# PID.net
KiCad netlist of a schematic drawn in EasyEDA Pro
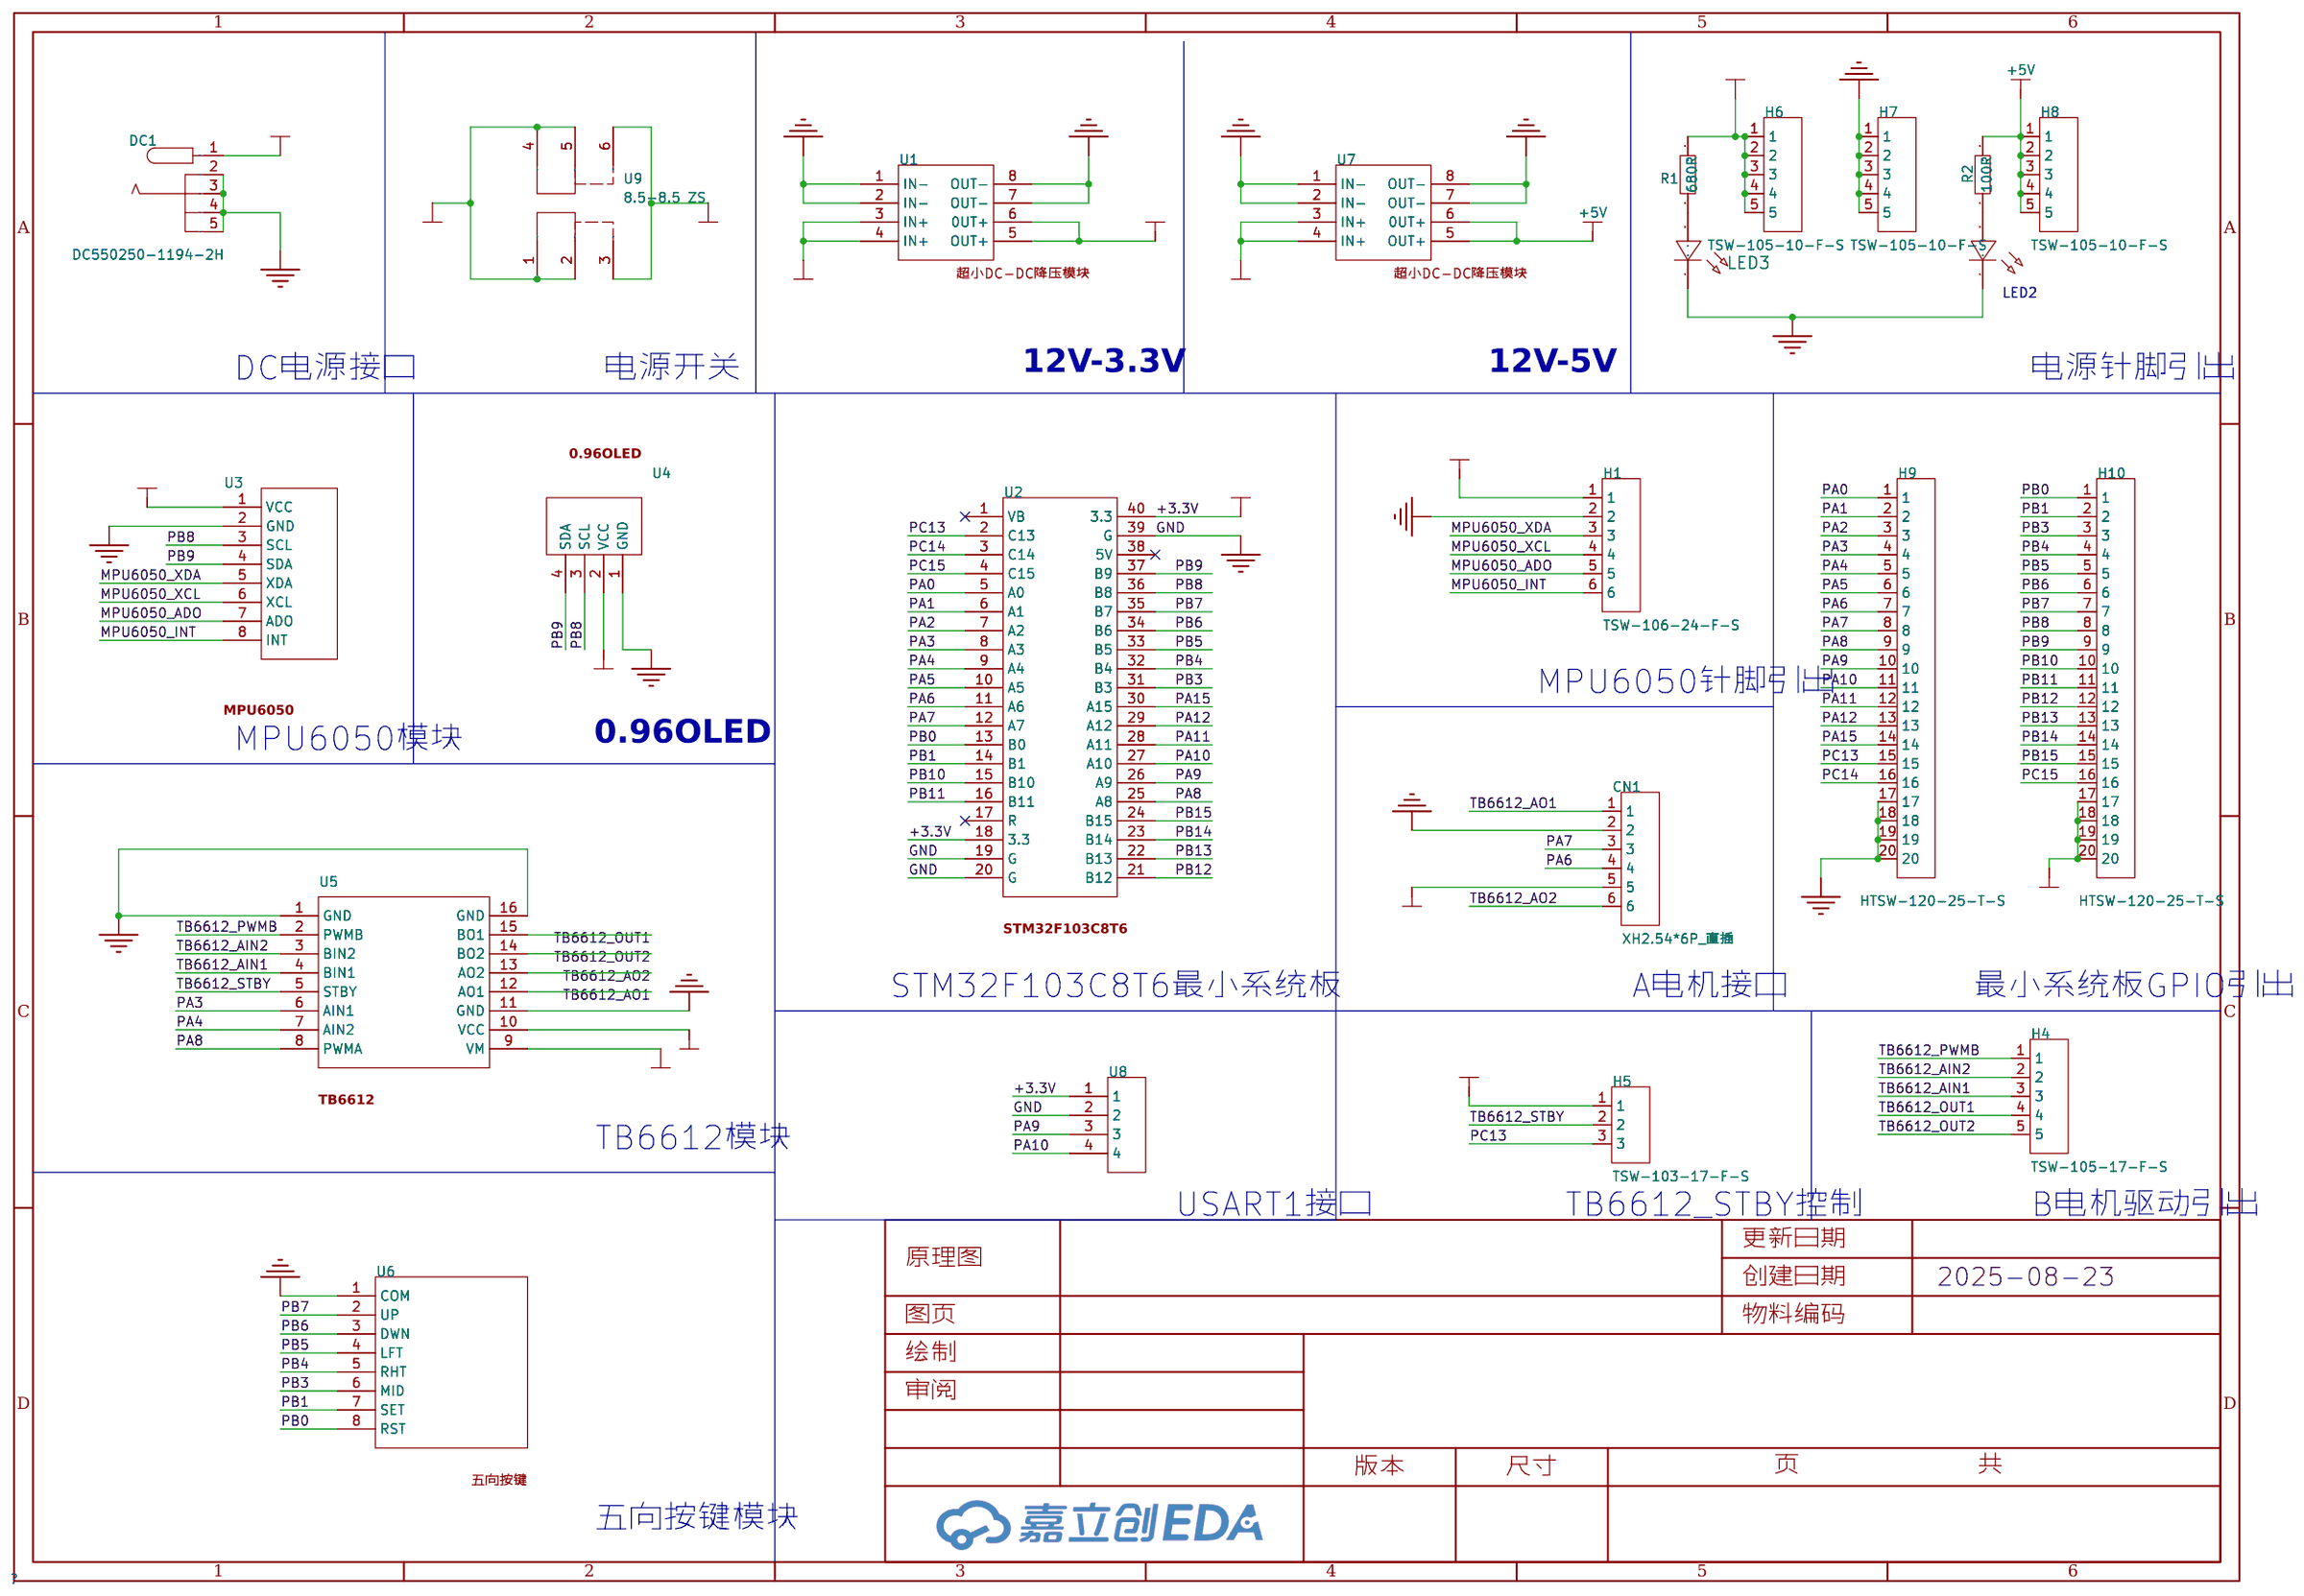
[diagram p0: schematic sheet]

(export (version "E")
  (design (tool "Eeschema 10.0.6"))
  (components
    (comp (ref "CN1")
      (value "XH2.54*6P_直插")
      (footprint "easyedapro:CONN-TH_XH2.54-6P")
      (libsource (lib "easyedapro") (part "XH2.54*6P_直插"))
    )
    (comp (ref "DC1")
      (value "DC550250-1194-2H")
      (footprint "easyedapro:DC-IN-TH_DC550250-1194-2H")
      (description "连接器类型:DC电源插座;")
      (fields (field (name "Manufacturer") "HDGC(华德共创)"))
      (libsource (lib "easyedapro") (part "DC550250-1194-2H"))
    )
    (comp (ref "H1")
      (value "TSW-106-24-F-S")
      (footprint "easyedapro:HDR-TH_MTSW-106-07-L-S-220")
      (description "间距:2.54mm;安装方式:直插;排数:单排;总PIN位数:6P;触头材质:磷青铜;触头镀层:锡;工作温度:-55°C~+125°C;颜色:黑色;")
      (fields (field (name "Manufacturer") "SAMTEC"))
      (libsource (lib "easyedapro") (part "TSW-106-24-F-S"))
    )
    (comp (ref "H4")
      (value "TSW-105-17-F-S")
      (footprint "easyedapro:HDR-TH_5P-P2.54_HTSW-105-08-F-S")
      (description "间距:2.54mm;安装方式:直插;排数:单排;总PIN位数:5P;触头材质:磷青铜;触头镀层:锡;工作温度:-55°C~+125°C;颜色:黑色;")
      (fields (field (name "Manufacturer") "SAMTEC"))
      (libsource (lib "easyedapro") (part "TSW-105-17-F-S"))
    )
    (comp (ref "H5")
      (value "TSW-103-17-F-S")
      (footprint "easyedapro:HDR-TH_3P-P2.54_HTSW-103-14-TM-S")
      (description "间距:2.54mm;安装方式:直插;排数:单排;总PIN位数:3P;触头材质:磷青铜;触头镀层:锡;工作温度:-55°C~+125°C;颜色:黑色;")
      (fields (field (name "Manufacturer") "SAMTEC"))
      (libsource (lib "easyedapro") (part "TSW-103-17-F-S"))
    )
    (comp (ref "H6")
      (value "TSW-105-10-F-S")
      (footprint "easyedapro:HDR-TH_5P-P2.54_HTSW-105-08-F-S")
      (description "间距:2.54mm;安装方式:直插;排数:单排;总PIN位数:5P;触头材质:磷青铜;触头镀层:锡;工作温度:-55°C~+125°C;颜色:黑色;")
      (fields (field (name "Manufacturer") "SAMTEC"))
      (libsource (lib "easyedapro") (part "TSW-105-10-F-S"))
    )
    (comp (ref "H7")
      (value "TSW-105-10-F-S")
      (footprint "easyedapro:HDR-TH_5P-P2.54_HTSW-105-08-F-S")
      (description "间距:2.54mm;安装方式:直插;排数:单排;总PIN位数:5P;触头材质:磷青铜;触头镀层:锡;工作温度:-55°C~+125°C;颜色:黑色;")
      (fields (field (name "Manufacturer") "SAMTEC"))
      (libsource (lib "easyedapro") (part "TSW-105-10-F-S"))
    )
    (comp (ref "H8")
      (value "TSW-105-10-F-S")
      (footprint "easyedapro:HDR-TH_5P-P2.54_HTSW-105-08-F-S")
      (description "间距:2.54mm;安装方式:直插;排数:单排;总PIN位数:5P;触头材质:磷青铜;触头镀层:锡;工作温度:-55°C~+125°C;颜色:黑色;")
      (fields (field (name "Manufacturer") "SAMTEC"))
      (libsource (lib "easyedapro") (part "TSW-105-10-F-S"))
    )
    (comp (ref "H9")
      (value "HTSW-120-25-T-S")
      (footprint "easyedapro:HDR-TH_TSW-120-22-L-S")
      (description "间距:2.54mm;安装方式:直插;排数:单排;总PIN位数:20P;触头材质:磷青铜;触头镀层:锡;工作温度:-55°C~+105°C;")
      (fields (field (name "Manufacturer") "SAMTEC"))
      (libsource (lib "easyedapro") (part "HTSW-120-25-T-S"))
    )
    (comp (ref "H10")
      (value "HTSW-120-25-T-S")
      (footprint "easyedapro:HDR-TH_TSW-120-22-L-S")
      (description "间距:2.54mm;安装方式:直插;排数:单排;总PIN位数:20P;触头材质:磷青铜;触头镀层:锡;工作温度:-55°C~+105°C;")
      (fields (field (name "Manufacturer") "SAMTEC"))
      (libsource (lib "easyedapro") (part "HTSW-120-25-T-S"))
    )
    (comp (ref "LED2")
      (value "~")
      (footprint "easyedapro:LED_0805")
      (libsource (lib "easyedapro") (part "LED_G"))
    )
    (comp (ref "LED3")
      (value "~")
      (footprint "easyedapro:LED_0805")
      (libsource (lib "easyedapro") (part "LED_R"))
    )
    (comp (ref "R1") (value "680R") (footprint "easyedapro:R0805") (libsource (lib "easyedapro") (part "电阻")))
    (comp (ref "R2") (value "100R") (footprint "easyedapro:R0805") (libsource (lib "easyedapro") (part "电阻")))
    (comp (ref "U1")
      (value "~")
      (footprint "easyedapro:12V-3.3V")
      (libsource (lib "easyedapro") (part "12V-3.3V"))
    )
    (comp (ref "U2")
      (value "~")
      (footprint "easyedapro:F103C8T6")
      (libsource (lib "easyedapro") (part "f103c8t6"))
    )
    (comp (ref "U3")
      (value "~")
      (footprint "easyedapro:MPU6050")
      (libsource (lib "easyedapro") (part "MPU6050"))
    )
    (comp (ref "U4")
      (value "~")
      (footprint "easyedapro:0.96OLED")
      (libsource (lib "easyedapro") (part "0.96OLED"))
    )
    (comp (ref "U5") (value "~") (footprint "easyedapro:电机驱动") (libsource (lib "easyedapro") (part "电机驱动")))
    (comp (ref "U6") (value "~") (footprint "easyedapro:五向按键") (libsource (lib "easyedapro") (part "五向按键")))
    (comp (ref "U7")
      (value "~")
      (footprint "easyedapro:12V-3.3V")
      (libsource (lib "easyedapro") (part "12V-3.3V"))
    )
    (comp (ref "U8") (value "~") (footprint "easyedapro:1x4") (libsource (lib "easyedapro") (part "1x4")))
    (comp (ref "U9")
      (value "8.5-8.5 ZS")
      (footprint "easyedapro:SW-TH_6P-L8.5-W8.5-P2.50_8.5-8.5-ZS")
      (description "电路结构:双刀双掷;自锁/无锁:自锁;安装方式:直插;触点电流:100mA;额定电压:30V;带灯:不带;作用力:1.8N;工作寿命:5千次;")
      (fields (field (name "Manufacturer") "SHOU HAN(首韩)"))
      (libsource (lib "easyedapro") (part "8.5-8.5 ZS"))
    )
  )
  (nets
    (net (code "1") (name "+3.3V") (class "Default")
      (node (ref "CN1") (pin "5") (pinfunction "5_5") (pintype "unspecified"))
      (node (ref "H1") (pin "1") (pinfunction "1_1") (pintype "unspecified"))
      (node (ref "H10") (pin "17") (pinfunction "17_17") (pintype "unspecified"))
      (node (ref "H10") (pin "18") (pinfunction "18_18") (pintype "unspecified"))
      (node (ref "H10") (pin "19") (pinfunction "19_19") (pintype "unspecified"))
      (node (ref "H10") (pin "20") (pinfunction "20_20") (pintype "unspecified"))
      (node (ref "H5") (pin "1") (pinfunction "1_1") (pintype "unspecified"))
      (node (ref "U1") (pin "5") (pinfunction "OUT+_5") (pintype "input"))
      (node (ref "U1") (pin "6") (pinfunction "0UT+_6") (pintype "input"))
      (node (ref "U2") (pin "18") (pinfunction "3.3_18") (pintype "input"))
      (node (ref "U2") (pin "40") (pinfunction "3.3_40") (pintype "input"))
      (node (ref "U3") (pin "1") (pinfunction "VCC_1") (pintype "input"))
      (node (ref "U4") (pin "2") (pinfunction "VCC_2") (pintype "input"))
      (node (ref "U5") (pin "10") (pinfunction "VCC_10") (pintype "input"))
      (node (ref "U8") (pin "1") (pinfunction "1_1") (pintype "input"))
    )
    (net (code "2") (name "+5V") (class "Default")
      (node (ref "H8") (pin "1") (pinfunction "1_1") (pintype "unspecified"))
      (node (ref "H8") (pin "2") (pinfunction "2_2") (pintype "unspecified"))
      (node (ref "H8") (pin "3") (pinfunction "3_3") (pintype "unspecified"))
      (node (ref "H8") (pin "4") (pinfunction "4_4") (pintype "unspecified"))
      (node (ref "H8") (pin "5") (pinfunction "5_5") (pintype "unspecified"))
      (node (ref "R2") (pin "2") (pinfunction "2_2") (pintype "input"))
      (node (ref "U7") (pin "5") (pinfunction "OUT+_5") (pintype "input"))
      (node (ref "U7") (pin "6") (pinfunction "0UT+_6") (pintype "input"))
    )
    (net (code "3") (name "+12V") (class "Default")
      (node (ref "H6") (pin "1") (pinfunction "1_1") (pintype "unspecified"))
      (node (ref "H6") (pin "2") (pinfunction "2_2") (pintype "unspecified"))
      (node (ref "H6") (pin "3") (pinfunction "3_3") (pintype "unspecified"))
      (node (ref "H6") (pin "4") (pinfunction "4_4") (pintype "unspecified"))
      (node (ref "H6") (pin "5") (pinfunction "5_5") (pintype "unspecified"))
      (node (ref "R1") (pin "1") (pinfunction "1_1") (pintype "input"))
      (node (ref "U1") (pin "3") (pinfunction "IN+_3") (pintype "input"))
      (node (ref "U1") (pin "4") (pinfunction "IN+_4") (pintype "input"))
      (node (ref "U5") (pin "9") (pinfunction "VM_9") (pintype "input"))
      (node (ref "U7") (pin "3") (pinfunction "IN+_3") (pintype "input"))
      (node (ref "U7") (pin "4") (pinfunction "IN+_4") (pintype "input"))
      (node (ref "U9") (pin "3") (pinfunction "3_3") (pintype "unspecified"))
      (node (ref "U9") (pin "6") (pinfunction "6_6") (pintype "unspecified"))
    )
    (net (code "4") (name "/MPU6050_ADO") (class "Default")
      (node (ref "H1") (pin "5") (pinfunction "5_5") (pintype "unspecified"))
      (node (ref "U3") (pin "7") (pinfunction "ADO_7") (pintype "input"))
    )
    (net (code "5") (name "/MPU6050_INT") (class "Default")
      (node (ref "H1") (pin "6") (pinfunction "6_6") (pintype "unspecified"))
      (node (ref "U3") (pin "8") (pinfunction "INT_8") (pintype "input"))
    )
    (net (code "6") (name "/MPU6050_XCL") (class "Default")
      (node (ref "H1") (pin "4") (pinfunction "4_4") (pintype "unspecified"))
      (node (ref "U3") (pin "6") (pinfunction "XCL_6") (pintype "input"))
    )
    (net (code "7") (name "/MPU6050_XDA") (class "Default")
      (node (ref "H1") (pin "3") (pinfunction "3_3") (pintype "unspecified"))
      (node (ref "U3") (pin "5") (pinfunction "XDA_5") (pintype "input"))
    )
    (net (code "8") (name "/PA0") (class "Default")
      (node (ref "H9") (pin "1") (pinfunction "1_1") (pintype "unspecified"))
      (node (ref "U2") (pin "5") (pinfunction "A0_5") (pintype "input"))
    )
    (net (code "9") (name "/PA1") (class "Default")
      (node (ref "H9") (pin "2") (pinfunction "2_2") (pintype "unspecified"))
      (node (ref "U2") (pin "6") (pinfunction "A1_6") (pintype "input"))
    )
    (net (code "10") (name "/PA2") (class "Default")
      (node (ref "H9") (pin "3") (pinfunction "3_3") (pintype "unspecified"))
      (node (ref "U2") (pin "7") (pinfunction "A2_7") (pintype "input"))
    )
    (net (code "11") (name "/PA3") (class "Default")
      (node (ref "H9") (pin "4") (pinfunction "4_4") (pintype "unspecified"))
      (node (ref "U2") (pin "8") (pinfunction "A3_8") (pintype "input"))
      (node (ref "U5") (pin "6") (pinfunction "AIN1_6") (pintype "input"))
    )
    (net (code "12") (name "/PA4") (class "Default")
      (node (ref "H9") (pin "5") (pinfunction "5_5") (pintype "unspecified"))
      (node (ref "U2") (pin "9") (pinfunction "A4_9") (pintype "input"))
      (node (ref "U5") (pin "7") (pinfunction "AIN2_7") (pintype "input"))
    )
    (net (code "13") (name "/PA5") (class "Default")
      (node (ref "H9") (pin "6") (pinfunction "6_6") (pintype "unspecified"))
      (node (ref "U2") (pin "10") (pinfunction "A5_10") (pintype "input"))
    )
    (net (code "14") (name "/PA6") (class "Default")
      (node (ref "CN1") (pin "4") (pinfunction "4_4") (pintype "unspecified"))
      (node (ref "H9") (pin "7") (pinfunction "7_7") (pintype "unspecified"))
      (node (ref "U2") (pin "11") (pinfunction "A6_11") (pintype "input"))
    )
    (net (code "15") (name "/PA7") (class "Default")
      (node (ref "CN1") (pin "3") (pinfunction "3_3") (pintype "unspecified"))
      (node (ref "H9") (pin "8") (pinfunction "8_8") (pintype "unspecified"))
      (node (ref "U2") (pin "12") (pinfunction "A7_12") (pintype "input"))
    )
    (net (code "16") (name "/PA8") (class "Default")
      (node (ref "H9") (pin "9") (pinfunction "9_9") (pintype "unspecified"))
      (node (ref "U2") (pin "25") (pinfunction "A8_25") (pintype "input"))
      (node (ref "U5") (pin "8") (pinfunction "PWMA_8") (pintype "input"))
    )
    (net (code "17") (name "/PA9") (class "Default")
      (node (ref "H9") (pin "10") (pinfunction "10_10") (pintype "unspecified"))
      (node (ref "U2") (pin "26") (pinfunction "A9_26") (pintype "input"))
      (node (ref "U8") (pin "3") (pinfunction "3_3") (pintype "input"))
    )
    (net (code "18") (name "/PA10") (class "Default")
      (node (ref "H9") (pin "11") (pinfunction "11_11") (pintype "unspecified"))
      (node (ref "U2") (pin "27") (pinfunction "A10_27") (pintype "input"))
      (node (ref "U8") (pin "4") (pinfunction "4_4") (pintype "input"))
    )
    (net (code "19") (name "/PA11") (class "Default")
      (node (ref "H9") (pin "12") (pinfunction "12_12") (pintype "unspecified"))
      (node (ref "U2") (pin "28") (pinfunction "A11_28") (pintype "input"))
    )
    (net (code "20") (name "/PA12") (class "Default")
      (node (ref "H9") (pin "13") (pinfunction "13_13") (pintype "unspecified"))
      (node (ref "U2") (pin "29") (pinfunction "A12_29") (pintype "input"))
    )
    (net (code "21") (name "/PA15") (class "Default")
      (node (ref "H9") (pin "14") (pinfunction "14_14") (pintype "unspecified"))
      (node (ref "U2") (pin "30") (pinfunction "A15_30") (pintype "input"))
    )
    (net (code "22") (name "/PB0") (class "Default")
      (node (ref "H10") (pin "1") (pinfunction "1_1") (pintype "unspecified"))
      (node (ref "U2") (pin "13") (pinfunction "B0_13") (pintype "input"))
      (node (ref "U6") (pin "8") (pinfunction "RST_8") (pintype "input"))
    )
    (net (code "23") (name "/PB1") (class "Default")
      (node (ref "H10") (pin "2") (pinfunction "2_2") (pintype "unspecified"))
      (node (ref "U2") (pin "14") (pinfunction "B1_14") (pintype "input"))
      (node (ref "U6") (pin "7") (pinfunction "SET_7") (pintype "input"))
    )
    (net (code "24") (name "/PB3") (class "Default")
      (node (ref "H10") (pin "3") (pinfunction "3_3") (pintype "unspecified"))
      (node (ref "U2") (pin "31") (pinfunction "B3_31") (pintype "input"))
      (node (ref "U6") (pin "6") (pinfunction "MID_6") (pintype "input"))
    )
    (net (code "25") (name "/PB4") (class "Default")
      (node (ref "H10") (pin "4") (pinfunction "4_4") (pintype "unspecified"))
      (node (ref "U2") (pin "32") (pinfunction "B4_32") (pintype "input"))
      (node (ref "U6") (pin "5") (pinfunction "RHT_5") (pintype "input"))
    )
    (net (code "26") (name "/PB5") (class "Default")
      (node (ref "H10") (pin "5") (pinfunction "5_5") (pintype "unspecified"))
      (node (ref "U2") (pin "33") (pinfunction "B5_33") (pintype "input"))
      (node (ref "U6") (pin "4") (pinfunction "LFT_4") (pintype "input"))
    )
    (net (code "27") (name "/PB6") (class "Default")
      (node (ref "H10") (pin "6") (pinfunction "6_6") (pintype "unspecified"))
      (node (ref "U2") (pin "34") (pinfunction "B6_34") (pintype "input"))
      (node (ref "U6") (pin "3") (pinfunction "DWN_3") (pintype "input"))
    )
    (net (code "28") (name "/PB7") (class "Default")
      (node (ref "H10") (pin "7") (pinfunction "7_7") (pintype "unspecified"))
      (node (ref "U2") (pin "35") (pinfunction "B7_35") (pintype "input"))
      (node (ref "U6") (pin "2") (pinfunction "UP_2") (pintype "input"))
    )
    (net (code "29") (name "/PB8") (class "Default")
      (node (ref "H10") (pin "8") (pinfunction "8_8") (pintype "unspecified"))
      (node (ref "U2") (pin "36") (pinfunction "B8_36") (pintype "input"))
      (node (ref "U3") (pin "3") (pinfunction "SCL_3") (pintype "input"))
      (node (ref "U4") (pin "3") (pinfunction "SCL_3") (pintype "input"))
    )
    (net (code "30") (name "/PB9") (class "Default")
      (node (ref "H10") (pin "9") (pinfunction "9_9") (pintype "unspecified"))
      (node (ref "U2") (pin "37") (pinfunction "B9_37") (pintype "input"))
      (node (ref "U3") (pin "4") (pinfunction "SDA_4") (pintype "input"))
      (node (ref "U4") (pin "4") (pinfunction "SDA_4") (pintype "input"))
    )
    (net (code "31") (name "/PB10") (class "Default")
      (node (ref "H10") (pin "10") (pinfunction "10_10") (pintype "unspecified"))
      (node (ref "U2") (pin "15") (pinfunction "B10_15") (pintype "input"))
    )
    (net (code "32") (name "/PB11") (class "Default")
      (node (ref "H10") (pin "11") (pinfunction "11_11") (pintype "unspecified"))
      (node (ref "U2") (pin "16") (pinfunction "B11_16") (pintype "input"))
    )
    (net (code "33") (name "/PB12") (class "Default")
      (node (ref "H10") (pin "12") (pinfunction "12_12") (pintype "unspecified"))
      (node (ref "U2") (pin "21") (pinfunction "B12_21") (pintype "input"))
    )
    (net (code "34") (name "/PB13") (class "Default")
      (node (ref "H10") (pin "13") (pinfunction "13_13") (pintype "unspecified"))
      (node (ref "U2") (pin "22") (pinfunction "B13_22") (pintype "input"))
    )
    (net (code "35") (name "/PB14") (class "Default")
      (node (ref "H10") (pin "14") (pinfunction "14_14") (pintype "unspecified"))
      (node (ref "U2") (pin "23") (pinfunction "B14_23") (pintype "input"))
    )
    (net (code "36") (name "/PB15") (class "Default")
      (node (ref "H10") (pin "15") (pinfunction "15_15") (pintype "unspecified"))
      (node (ref "U2") (pin "24") (pinfunction "B15_24") (pintype "input"))
    )
    (net (code "37") (name "/PC13") (class "Default")
      (node (ref "H5") (pin "3") (pinfunction "3_3") (pintype "unspecified"))
      (node (ref "H9") (pin "15") (pinfunction "15_15") (pintype "unspecified"))
      (node (ref "U2") (pin "2") (pinfunction "C13_2") (pintype "input"))
    )
    (net (code "38") (name "/PC14") (class "Default")
      (node (ref "H9") (pin "16") (pinfunction "16_16") (pintype "unspecified"))
      (node (ref "U2") (pin "3") (pinfunction "C14_3") (pintype "input"))
    )
    (net (code "39") (name "/PC15") (class "Default")
      (node (ref "H10") (pin "16") (pinfunction "16_16") (pintype "unspecified"))
      (node (ref "U2") (pin "4") (pinfunction "C15_4") (pintype "input"))
    )
    (net (code "40") (name "/TB6612_AIN1") (class "Default")
      (node (ref "H4") (pin "3") (pinfunction "3_3") (pintype "unspecified"))
      (node (ref "U5") (pin "4") (pinfunction "BIN1_4") (pintype "input"))
    )
    (net (code "41") (name "/TB6612_AIN2") (class "Default")
      (node (ref "H4") (pin "2") (pinfunction "2_2") (pintype "unspecified"))
      (node (ref "U5") (pin "3") (pinfunction "BIN2_3") (pintype "input"))
    )
    (net (code "42") (name "/TB6612_AO1") (class "Default")
      (node (ref "CN1") (pin "1") (pinfunction "1_1") (pintype "unspecified"))
      (node (ref "U5") (pin "12") (pinfunction "AO1_12") (pintype "input"))
    )
    (net (code "43") (name "/TB6612_AO2") (class "Default")
      (node (ref "CN1") (pin "6") (pinfunction "6_6") (pintype "unspecified"))
      (node (ref "U5") (pin "13") (pinfunction "AO2_13") (pintype "input"))
    )
    (net (code "44") (name "/TB6612_OUT1") (class "Default")
      (node (ref "H4") (pin "4") (pinfunction "4_4") (pintype "unspecified"))
      (node (ref "U5") (pin "15") (pinfunction "BO1_15") (pintype "input"))
    )
    (net (code "45") (name "/TB6612_OUT2") (class "Default")
      (node (ref "H4") (pin "5") (pinfunction "5_5") (pintype "unspecified"))
      (node (ref "U5") (pin "14") (pinfunction "BO2_14") (pintype "input"))
    )
    (net (code "46") (name "/TB6612_PWMB") (class "Default")
      (node (ref "H4") (pin "1") (pinfunction "1_1") (pintype "unspecified"))
      (node (ref "U5") (pin "2") (pinfunction "PWMB_2") (pintype "input"))
    )
    (net (code "47") (name "/TB6612_STBY") (class "Default")
      (node (ref "H5") (pin "2") (pinfunction "2_2") (pintype "unspecified"))
      (node (ref "U5") (pin "5") (pinfunction "STBY_5") (pintype "input"))
    )
    (net (code "48") (name "GND") (class "Default")
      (node (ref "CN1") (pin "2") (pinfunction "2_2") (pintype "unspecified"))
      (node (ref "DC1") (pin "2") (pinfunction "-_2") (pintype "unspecified"))
      (node (ref "DC1") (pin "3") (pinfunction "-_3") (pintype "unspecified"))
      (node (ref "DC1") (pin "4") (pinfunction "-_4") (pintype "unspecified"))
      (node (ref "DC1") (pin "5") (pinfunction "-_5") (pintype "unspecified"))
      (node (ref "H1") (pin "2") (pinfunction "2_2") (pintype "unspecified"))
      (node (ref "H7") (pin "1") (pinfunction "1_1") (pintype "unspecified"))
      (node (ref "H7") (pin "2") (pinfunction "2_2") (pintype "unspecified"))
      (node (ref "H7") (pin "3") (pinfunction "3_3") (pintype "unspecified"))
      (node (ref "H7") (pin "4") (pinfunction "4_4") (pintype "unspecified"))
      (node (ref "H7") (pin "5") (pinfunction "5_5") (pintype "unspecified"))
      (node (ref "H9") (pin "17") (pinfunction "17_17") (pintype "unspecified"))
      (node (ref "H9") (pin "18") (pinfunction "18_18") (pintype "unspecified"))
      (node (ref "H9") (pin "19") (pinfunction "19_19") (pintype "unspecified"))
      (node (ref "H9") (pin "20") (pinfunction "20_20") (pintype "unspecified"))
      (node (ref "LED2") (pin "1") (pinfunction "C_1") (pintype "input"))
      (node (ref "LED3") (pin "1") (pinfunction "C_1") (pintype "input"))
      (node (ref "U1") (pin "1") (pinfunction "IN-_1") (pintype "input"))
      (node (ref "U1") (pin "2") (pinfunction "IN-_2") (pintype "input"))
      (node (ref "U1") (pin "7") (pinfunction "OUT-_7") (pintype "input"))
      (node (ref "U1") (pin "8") (pinfunction "OUT-_8") (pintype "input"))
      (node (ref "U2") (pin "19") (pinfunction "G_19") (pintype "input"))
      (node (ref "U2") (pin "20") (pinfunction "G_20") (pintype "input"))
      (node (ref "U2") (pin "39") (pinfunction "G_39") (pintype "input"))
      (node (ref "U3") (pin "2") (pinfunction "GND_2") (pintype "input"))
      (node (ref "U4") (pin "1") (pinfunction "GND_1") (pintype "input"))
      (node (ref "U5") (pin "1") (pinfunction "GND_1") (pintype "input"))
      (node (ref "U5") (pin "11") (pinfunction "GND_11") (pintype "input"))
      (node (ref "U5") (pin "16") (pinfunction "GND_16") (pintype "input"))
      (node (ref "U6") (pin "1") (pinfunction "COM_1") (pintype "input"))
      (node (ref "U7") (pin "1") (pinfunction "IN-_1") (pintype "input"))
      (node (ref "U7") (pin "2") (pinfunction "IN-_2") (pintype "input"))
      (node (ref "U7") (pin "7") (pinfunction "OUT-_7") (pintype "input"))
      (node (ref "U7") (pin "8") (pinfunction "OUT-_8") (pintype "input"))
      (node (ref "U8") (pin "2") (pinfunction "2_2") (pintype "input"))
    )
    (net (code "49") (name "IN+12V") (class "Default")
      (node (ref "DC1") (pin "1") (pinfunction "+_1") (pintype "unspecified"))
      (node (ref "U9") (pin "1") (pinfunction "1_1") (pintype "unspecified"))
      (node (ref "U9") (pin "2") (pinfunction "2_2") (pintype "unspecified"))
      (node (ref "U9") (pin "4") (pinfunction "4_4") (pintype "unspecified"))
      (node (ref "U9") (pin "5") (pinfunction "5_5") (pintype "unspecified"))
    )
    (net (code "50") (name "Net-(LED2-A)") (class "Default")
      (node (ref "LED2") (pin "2") (pinfunction "A_2") (pintype "input"))
      (node (ref "R2") (pin "1") (pinfunction "1_1") (pintype "input"))
    )
    (net (code "51") (name "Net-(LED3-A)") (class "Default")
      (node (ref "LED3") (pin "2") (pinfunction "A_2") (pintype "input"))
      (node (ref "R1") (pin "2") (pinfunction "2_2") (pintype "input"))
    )
    (net (code "52") (name "unconnected-(U2-5V-Pad38)") (class "Default")
      (node (ref "U2") (pin "38") (pinfunction "5V_38") (pintype "input+no_connect"))
    )
    (net (code "53") (name "unconnected-(U2-R-Pad17)") (class "Default")
      (node (ref "U2") (pin "17") (pinfunction "R_17") (pintype "input+no_connect"))
    )
    (net (code "54") (name "unconnected-(U2-VB-Pad1)") (class "Default")
      (node (ref "U2") (pin "1") (pinfunction "VB_1") (pintype "input+no_connect"))
    )
  )
)
